# Varella_Std_-_v_1_0.net
KiCad netlist of a schematic drawn in EAGLE
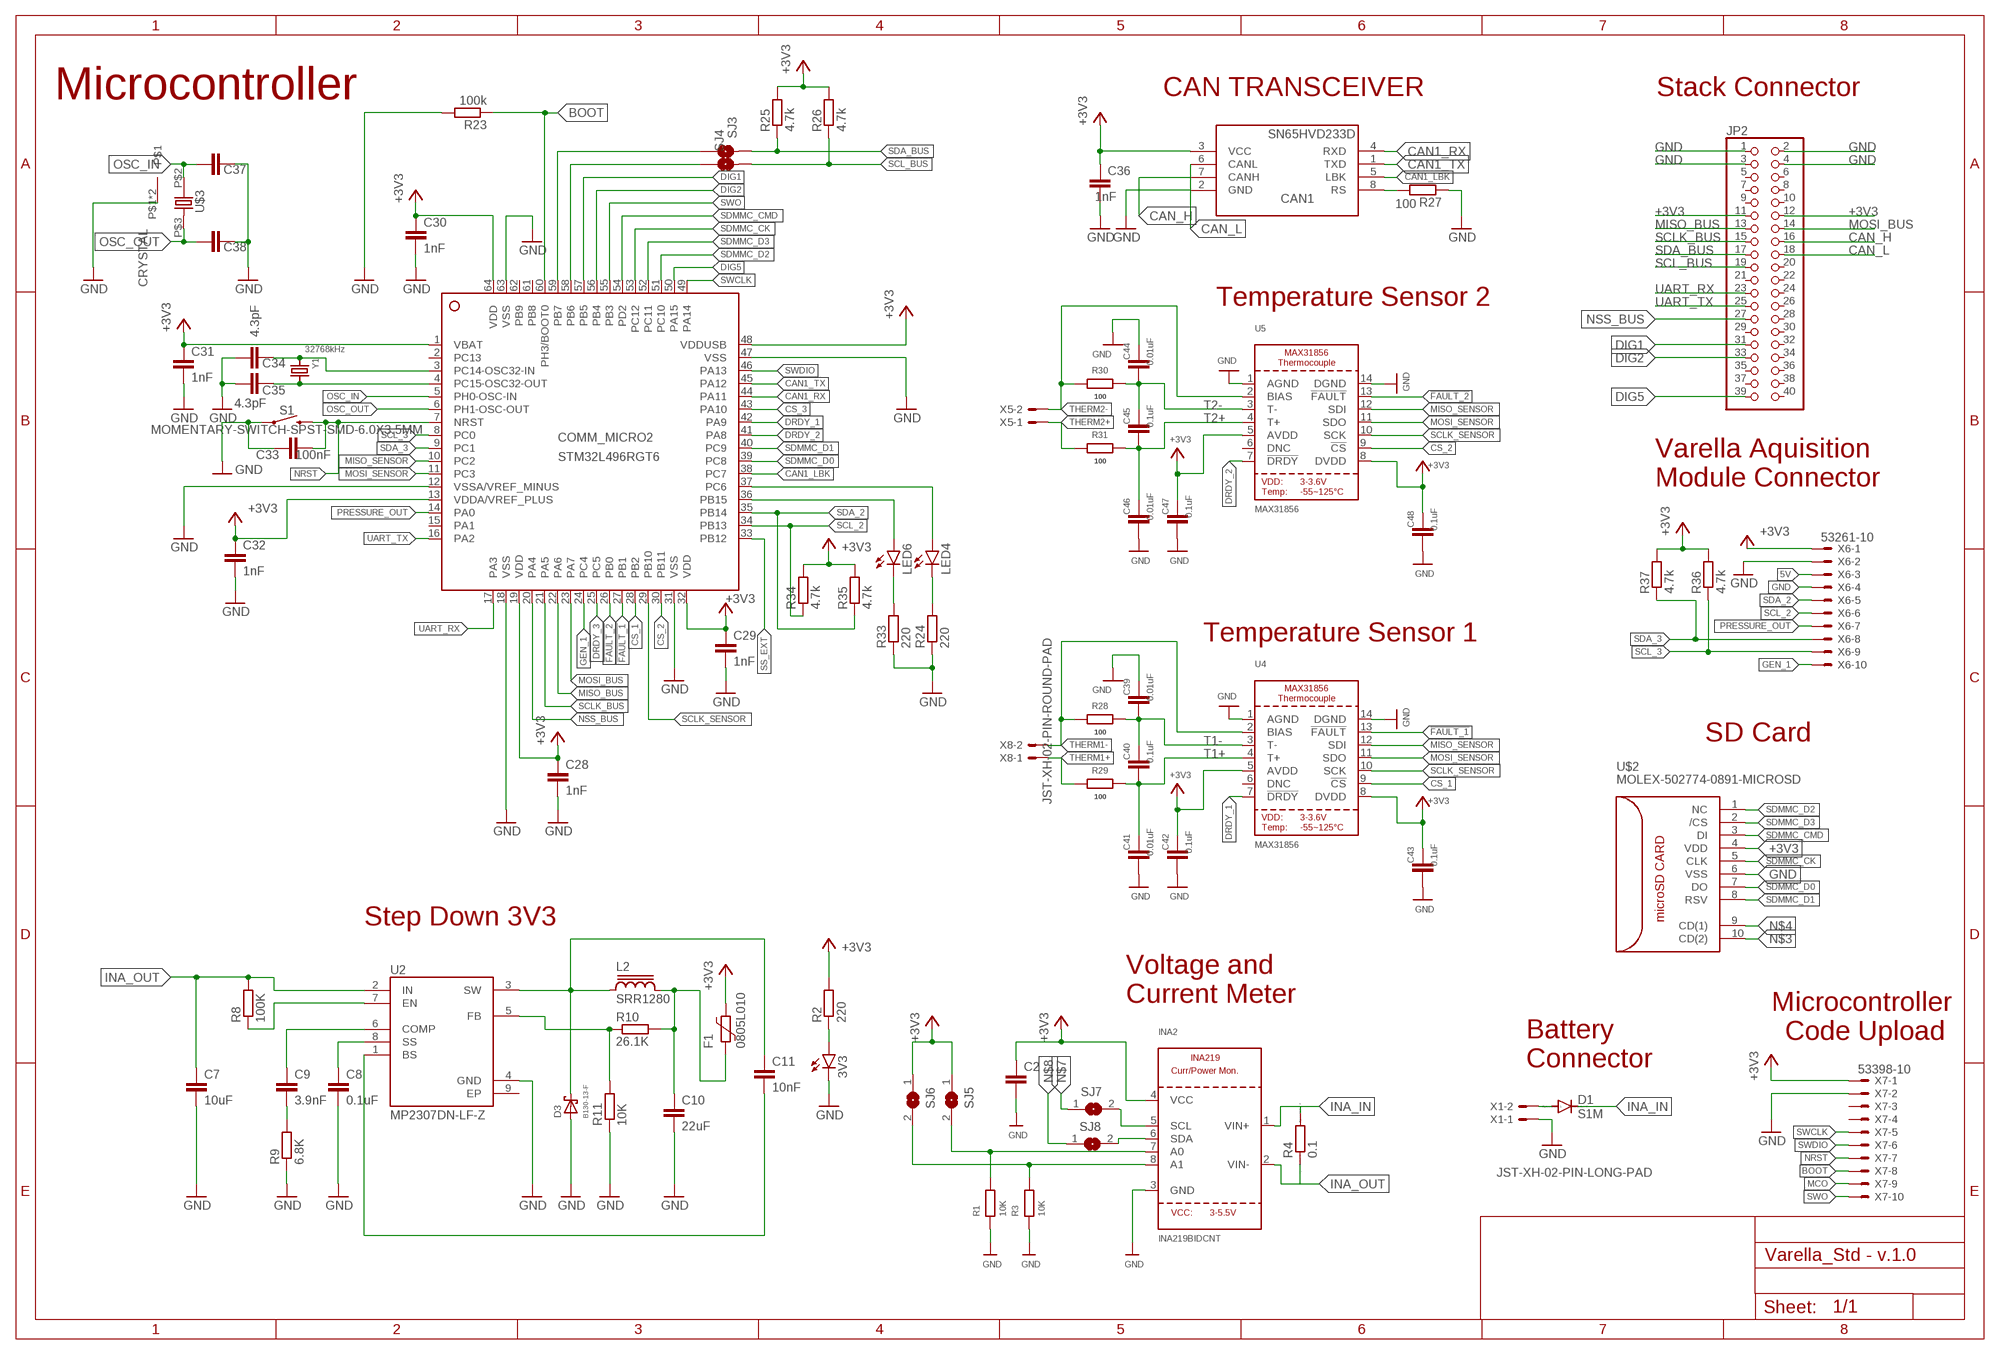
[diagram p0: schematic, sheet 1]

(export (version "E")
  (design (tool "Eeschema 10.0.6"))
  (components
    (comp (ref "3V3")
      (value "LEDCHIP-LED0805")
      (footprint "eagle-import:CHIP-LED0805")
      (libsource (lib "eagle-import") (part "LEDCHIP-LED0805"))
    )
    (comp (ref "C2")
      (value "C-EUC0805")
      (footprint "eagle-import:C0805")
      (libsource (lib "eagle-import") (part "C-EUC0805"))
    )
    (comp (ref "C7")
      (value "10uF")
      (footprint "eagle-import:C0805")
      (libsource (lib "eagle-import") (part "C-EUC0805"))
    )
    (comp (ref "C8")
      (value "0.1uF")
      (footprint "eagle-import:C0805")
      (libsource (lib "eagle-import") (part "C-EUC0805"))
    )
    (comp (ref "C9")
      (value "3.9nF")
      (footprint "eagle-import:C0805")
      (libsource (lib "eagle-import") (part "C-EUC0805"))
    )
    (comp (ref "C10")
      (value "22uF")
      (footprint "eagle-import:C0805")
      (libsource (lib "eagle-import") (part "C-EUC0805"))
    )
    (comp (ref "C11")
      (value "10nF")
      (footprint "eagle-import:C0805")
      (libsource (lib "eagle-import") (part "C-EUC0805"))
    )
    (comp (ref "C28")
      (value "1nF")
      (footprint "eagle-import:C0805")
      (libsource (lib "eagle-import") (part "C-EUC0805"))
    )
    (comp (ref "C29")
      (value "1nF")
      (footprint "eagle-import:C0805")
      (libsource (lib "eagle-import") (part "C-EUC0805"))
    )
    (comp (ref "C30")
      (value "1nF")
      (footprint "eagle-import:C0805")
      (libsource (lib "eagle-import") (part "C-EUC0805"))
    )
    (comp (ref "C31")
      (value "1nF")
      (footprint "eagle-import:C0805")
      (libsource (lib "eagle-import") (part "C-EUC0805"))
    )
    (comp (ref "C32")
      (value "1nF")
      (footprint "eagle-import:C0805")
      (libsource (lib "eagle-import") (part "C-EUC0805"))
    )
    (comp (ref "C33")
      (value "100nF")
      (footprint "eagle-import:C0805")
      (libsource (lib "eagle-import") (part "C-EUC0805"))
    )
    (comp (ref "C34")
      (value "4.3pF")
      (footprint "eagle-import:C0805")
      (libsource (lib "eagle-import") (part "C-EUC0805"))
    )
    (comp (ref "C35")
      (value "4.3pF")
      (footprint "eagle-import:C0805")
      (libsource (lib "eagle-import") (part "C-EUC0805"))
    )
    (comp (ref "C36")
      (value "1nF")
      (footprint "eagle-import:C0805")
      (libsource (lib "eagle-import") (part "C-EUC0805"))
    )
    (comp (ref "C37")
      (value "C-EUC0805")
      (footprint "eagle-import:C0805")
      (libsource (lib "eagle-import") (part "C-EUC0805"))
    )
    (comp (ref "C38")
      (value "C-EUC0805")
      (footprint "eagle-import:C0805")
      (libsource (lib "eagle-import") (part "C-EUC0805"))
    )
    (comp (ref "C39")
      (value "0.01uF")
      (footprint "eagle-import:C0805")
      (libsource (lib "eagle-import") (part "C-EUC0805"))
    )
    (comp (ref "C40")
      (value "0.1uF")
      (footprint "eagle-import:C0805")
      (libsource (lib "eagle-import") (part "C-EUC0805"))
    )
    (comp (ref "C41")
      (value "0.01uF")
      (footprint "eagle-import:C0805")
      (libsource (lib "eagle-import") (part "C-EUC0805"))
    )
    (comp (ref "C42")
      (value "0.1uF")
      (footprint "eagle-import:C0805")
      (libsource (lib "eagle-import") (part "C-EUC0805"))
    )
    (comp (ref "C43")
      (value "0.1uF")
      (footprint "eagle-import:C0805")
      (libsource (lib "eagle-import") (part "C-EUC0805"))
    )
    (comp (ref "C44")
      (value "0.01uF")
      (footprint "eagle-import:C0805")
      (libsource (lib "eagle-import") (part "C-EUC0805"))
    )
    (comp (ref "C45")
      (value "0.1uF")
      (footprint "eagle-import:C0805")
      (libsource (lib "eagle-import") (part "C-EUC0805"))
    )
    (comp (ref "C46")
      (value "0.01uF")
      (footprint "eagle-import:C0805")
      (libsource (lib "eagle-import") (part "C-EUC0805"))
    )
    (comp (ref "C47")
      (value "0.1uF")
      (footprint "eagle-import:C0805")
      (libsource (lib "eagle-import") (part "C-EUC0805"))
    )
    (comp (ref "C48")
      (value "0.1uF")
      (footprint "eagle-import:C0805")
      (libsource (lib "eagle-import") (part "C-EUC0805"))
    )
    (comp (ref "CAN1")
      (value "SN65HVD233D")
      (footprint "eagle-import:SOIC8")
      (fields (field (name "MF") "Texas Instruments"))
      (libsource (lib "eagle-import") (part "SN65HVD233D"))
    )
    (comp (ref "COMM_MICRO2")
      (value "STM32L496RGT6")
      (footprint "eagle-import:LQFP64_10X10")
      (libsource (lib "eagle-import") (part "STM32L496RGT6"))
    )
    (comp (ref "D1")
      (value "S1M")
      (footprint "eagle-import:SMA")
      (libsource (lib "eagle-import") (part "S1M"))
    )
    (comp (ref "D3")
      (value "B130-13-F")
      (footprint "eagle-import:SMA")
      (fields (field (name "MF") "Multicomp"))
      (libsource (lib "eagle-import") (part "B130-13-F"))
    )
    (comp (ref "F1")
      (value "0805L010")
      (footprint "eagle-import:0805L")
      (fields (field (name "MF") "Littelfuse"))
      (libsource (lib "eagle-import") (part "?0805L010"))
    )
    (comp (ref "INA2")
      (value "INA219BIDCNT")
      (footprint "eagle-import:SOT23-8")
      (libsource (lib "eagle-import") (part "INA219"))
    )
    (comp (ref "JP2")
      (value "PINHD-2X20")
      (footprint "eagle-import:2X20")
      (libsource (lib "eagle-import") (part "PINHD-2X20"))
    )
    (comp (ref "L2")
      (value "SRR1280")
      (footprint "eagle-import:SRR1280")
      (libsource (lib "eagle-import") (part "SRR1280"))
    )
    (comp (ref "LED4")
      (value "LEDCHIP-LED0805")
      (footprint "eagle-import:CHIP-LED0805")
      (libsource (lib "eagle-import") (part "LEDCHIP-LED0805"))
    )
    (comp (ref "LED6")
      (value "LEDCHIP-LED0805")
      (footprint "eagle-import:CHIP-LED0805")
      (libsource (lib "eagle-import") (part "LEDCHIP-LED0805"))
    )
    (comp (ref "R1")
      (value "10K")
      (footprint "eagle-import:R0805")
      (libsource (lib "eagle-import") (part "R-EU_R0805"))
    )
    (comp (ref "R2")
      (value "220")
      (footprint "eagle-import:R0805")
      (libsource (lib "eagle-import") (part "R-EU_R0805"))
    )
    (comp (ref "R3")
      (value "10K")
      (footprint "eagle-import:R0805")
      (libsource (lib "eagle-import") (part "R-EU_R0805"))
    )
    (comp (ref "R4")
      (value "0.1")
      (footprint "eagle-import:R2512")
      (libsource (lib "eagle-import") (part "RR2512"))
    )
    (comp (ref "R8")
      (value "100K")
      (footprint "eagle-import:R0805")
      (libsource (lib "eagle-import") (part "R-EU_R0805"))
    )
    (comp (ref "R9")
      (value "6.8K")
      (footprint "eagle-import:R0805")
      (libsource (lib "eagle-import") (part "R-EU_R0805"))
    )
    (comp (ref "R10")
      (value "26.1K")
      (footprint "eagle-import:R0805")
      (libsource (lib "eagle-import") (part "R-EU_R0805"))
    )
    (comp (ref "R11")
      (value "10K")
      (footprint "eagle-import:R0805")
      (libsource (lib "eagle-import") (part "R-EU_R0805"))
    )
    (comp (ref "R23")
      (value "100k")
      (footprint "eagle-import:R0805")
      (libsource (lib "eagle-import") (part "R-EU_R0805"))
    )
    (comp (ref "R24")
      (value "220")
      (footprint "eagle-import:R0805")
      (libsource (lib "eagle-import") (part "R-EU_R0805"))
    )
    (comp (ref "R25")
      (value "4.7k")
      (footprint "eagle-import:R0805")
      (libsource (lib "eagle-import") (part "R-EU_R0805"))
    )
    (comp (ref "R26")
      (value "4.7k")
      (footprint "eagle-import:R0805")
      (libsource (lib "eagle-import") (part "R-EU_R0805"))
    )
    (comp (ref "R27")
      (value "100")
      (footprint "eagle-import:R0805")
      (libsource (lib "eagle-import") (part "R-EU_R0805"))
    )
    (comp (ref "R28")
      (value "100")
      (footprint "eagle-import:R0805")
      (libsource (lib "eagle-import") (part "R-EU_R0805"))
    )
    (comp (ref "R29")
      (value "100")
      (footprint "eagle-import:R0805")
      (libsource (lib "eagle-import") (part "R-EU_R0805"))
    )
    (comp (ref "R30")
      (value "100")
      (footprint "eagle-import:R0805")
      (libsource (lib "eagle-import") (part "R-EU_R0805"))
    )
    (comp (ref "R31")
      (value "100")
      (footprint "eagle-import:R0805")
      (libsource (lib "eagle-import") (part "R-EU_R0805"))
    )
    (comp (ref "R33")
      (value "220")
      (footprint "eagle-import:R0805")
      (libsource (lib "eagle-import") (part "R-EU_R0805"))
    )
    (comp (ref "R34")
      (value "4.7k")
      (footprint "eagle-import:R0805")
      (libsource (lib "eagle-import") (part "R-EU_R0805"))
    )
    (comp (ref "R35")
      (value "4.7k")
      (footprint "eagle-import:R0805")
      (libsource (lib "eagle-import") (part "R-EU_R0805"))
    )
    (comp (ref "R36")
      (value "4.7k")
      (footprint "eagle-import:R0805")
      (libsource (lib "eagle-import") (part "R-EU_R0805"))
    )
    (comp (ref "R37")
      (value "4.7k")
      (footprint "eagle-import:R0805")
      (libsource (lib "eagle-import") (part "R-EU_R0805"))
    )
    (comp (ref "S1")
      (value "MOMENTARY-SWITCH-SPST-SMD-6.0X3.5MM")
      (footprint "eagle-import:TACTILE_SWITCH_SMD_6.0X3.5MM")
      (libsource (lib "eagle-import") (part "MOMENTARY-SWITCH-SPST-SMD-6.0X3.5MM"))
    )
    (comp (ref "SJ3")
      (value "SMD-JUMPER-2")
      (footprint "eagle-import:SMD-JUMPER-2")
      (libsource (lib "eagle-import") (part "SMD-JUMPER-2"))
    )
    (comp (ref "SJ4")
      (value "SMD-JUMPER-2")
      (footprint "eagle-import:SMD-JUMPER-2")
      (libsource (lib "eagle-import") (part "SMD-JUMPER-2"))
    )
    (comp (ref "SJ5")
      (value "SOLDERJUMPERREFLOW_NOPASTE")
      (footprint "eagle-import:SOLDERJUMPER_REFLOW_NOPASTE")
      (libsource (lib "eagle-import") (part "SOLDERJUMPERREFLOW_NOPASTE"))
    )
    (comp (ref "SJ6")
      (value "SOLDERJUMPERREFLOW_NOPASTE")
      (footprint "eagle-import:SOLDERJUMPER_REFLOW_NOPASTE")
      (libsource (lib "eagle-import") (part "SOLDERJUMPERREFLOW_NOPASTE"))
    )
    (comp (ref "SJ7")
      (value "SOLDERJUMPERREFLOW_NOPASTE")
      (footprint "eagle-import:SOLDERJUMPER_REFLOW_NOPASTE")
      (libsource (lib "eagle-import") (part "SOLDERJUMPERREFLOW_NOPASTE"))
    )
    (comp (ref "SJ8")
      (value "SOLDERJUMPERREFLOW_NOPASTE")
      (footprint "eagle-import:SOLDERJUMPER_REFLOW_NOPASTE")
      (libsource (lib "eagle-import") (part "SOLDERJUMPERREFLOW_NOPASTE"))
    )
    (comp (ref "U$2")
      (value "MOLEX-502774-0891-MICROSD")
      (footprint "eagle-import:MOLEX-502774-0891-MICROSD")
      (libsource (lib "eagle-import") (part "MOLEX-502774-0891-MICROSD"))
    )
    (comp (ref "U$3")
      (value "CRYSTAL")
      (footprint "eagle-import:CRYSTAL_SMD")
      (libsource (lib "eagle-import") (part "CRYSTAL"))
    )
    (comp (ref "U2")
      (value "MP2307DN-LF-Z")
      (footprint "eagle-import:SOIC127P600X170-9N")
      (fields (field (name "MF") "Monolithic Power"))
      (libsource (lib "eagle-import") (part "MP2307DN-LF-Z"))
    )
    (comp (ref "U4")
      (value "MAX31856")
      (footprint "eagle-import:TSSOP14")
      (libsource (lib "eagle-import") (part "MAX31856"))
    )
    (comp (ref "U5")
      (value "MAX31856")
      (footprint "eagle-import:TSSOP14")
      (libsource (lib "eagle-import") (part "MAX31856"))
    )
    (comp (ref "X1")
      (value "JST-XH-02-PIN-LONG-PAD")
      (footprint "eagle-import:JST-XH-02-PACKAGE-LONG-PAD")
      (libsource (lib "eagle-import") (part "JST-XH-02-PIN-LONG-PAD"))
    )
    (comp (ref "X5")
      (value "JST-XH-02-PIN-ROUND-PAD")
      (footprint "eagle-import:JST-XH-02-PACKAGE-ROUND-PAD")
      (libsource (lib "eagle-import") (part "JST-XH-02-PIN-ROUND-PAD"))
    )
    (comp (ref "X6")
      (value "53261-10")
      (footprint "eagle-import:53261-10")
      (fields (field (name "MF") "MOLEX"))
      (libsource (lib "eagle-import") (part "con-zenith_17020879_53?-10261"))
    )
    (comp (ref "X7")
      (value "53398-10")
      (footprint "eagle-import:53398-10")
      (fields (field (name "MF") "MOLEX") (field (name "MPN") "53398-1071"))
      (libsource (lib "eagle-import") (part "53?-10398"))
    )
    (comp (ref "X8")
      (value "JST-XH-02-PIN-ROUND-PAD")
      (footprint "eagle-import:JST-XH-02-PACKAGE-ROUND-PAD")
      (libsource (lib "eagle-import") (part "JST-XH-02-PIN-ROUND-PAD"))
    )
    (comp (ref "Y1")
      (value "32768kHz")
      (footprint "eagle-import:CRYSTAL_8X3.8")
      (libsource (lib "eagle-import") (part "CRYSTAL8X3.8SMT"))
    )
  )
  (nets
    (net (code "1") (name "+3V3") (class "Default")
      (node (ref "C2") (pin "1") (pinfunction "1_1") (pintype "passive"))
      (node (ref "C28") (pin "1") (pinfunction "1_1") (pintype "passive"))
      (node (ref "C29") (pin "1") (pinfunction "1_1") (pintype "passive"))
      (node (ref "C30") (pin "1") (pinfunction "1_1") (pintype "passive"))
      (node (ref "C31") (pin "1") (pinfunction "1_1") (pintype "passive"))
      (node (ref "C32") (pin "1") (pinfunction "1_1") (pintype "passive"))
      (node (ref "C36") (pin "1") (pinfunction "1_1") (pintype "passive"))
      (node (ref "C42") (pin "1") (pinfunction "1_1") (pintype "passive"))
      (node (ref "C43") (pin "1") (pinfunction "1_1") (pintype "passive"))
      (node (ref "C47") (pin "1") (pinfunction "1_1") (pintype "passive"))
      (node (ref "C48") (pin "1") (pinfunction "1_1") (pintype "passive"))
      (node (ref "CAN1") (pin "3") (pinfunction "VCC_3") (pintype "power_in"))
      (node (ref "COMM_MICRO2") (pin "1") (pinfunction "VBAT_1") (pintype "passive"))
      (node (ref "COMM_MICRO2") (pin "13") (pinfunction "VDDA/VREF_PLUS_13") (pintype "passive"))
      (node (ref "COMM_MICRO2") (pin "19") (pinfunction "VDD_19") (pintype "power_in"))
      (node (ref "COMM_MICRO2") (pin "32") (pinfunction "VDD_32") (pintype "power_in"))
      (node (ref "COMM_MICRO2") (pin "48") (pinfunction "VDDUSB_48") (pintype "bidirectional"))
      (node (ref "COMM_MICRO2") (pin "64") (pinfunction "VDD_64") (pintype "power_in"))
      (node (ref "F1") (pin "1") (pinfunction "1_1") (pintype "passive"))
      (node (ref "INA2") (pin "4") (pinfunction "VCC_4") (pintype "bidirectional"))
      (node (ref "JP2") (pin "11") (pinfunction "11_11") (pintype "passive"))
      (node (ref "JP2") (pin "12") (pinfunction "12_12") (pintype "passive"))
      (node (ref "R2") (pin "2") (pinfunction "2_2") (pintype "passive"))
      (node (ref "R25") (pin "2") (pinfunction "2_2") (pintype "passive"))
      (node (ref "R26") (pin "2") (pinfunction "2_2") (pintype "passive"))
      (node (ref "R34") (pin "2") (pinfunction "2_2") (pintype "passive"))
      (node (ref "R35") (pin "2") (pinfunction "2_2") (pintype "passive"))
      (node (ref "R36") (pin "2") (pinfunction "2_2") (pintype "passive"))
      (node (ref "R37") (pin "2") (pinfunction "2_2") (pintype "passive"))
      (node (ref "SJ5") (pin "1") (pinfunction "1_1") (pintype "passive"))
      (node (ref "SJ6") (pin "1") (pinfunction "1_1") (pintype "passive"))
      (node (ref "U$2") (pin "4") (pinfunction "VDD_4") (pintype "bidirectional"))
      (node (ref "U4") (pin "5") (pinfunction "AVDD_5") (pintype "power_in"))
      (node (ref "U4") (pin "8") (pinfunction "DVDD_8") (pintype "power_in"))
      (node (ref "U5") (pin "5") (pinfunction "AVDD_5") (pintype "power_in"))
      (node (ref "U5") (pin "8") (pinfunction "DVDD_8") (pintype "power_in"))
      (node (ref "X6") (pin "1") (pinfunction "S_1") (pintype "passive"))
      (node (ref "X7") (pin "1") (pinfunction "S_1") (pintype "passive"))
    )
    (net (code "2") (name "/EP") (class "Default")
      (node (ref "U2") (pin "9") (pinfunction "EP_9") (pintype "power_in"))
    )
    (net (code "3") (name "/T1+") (class "Default")
      (node (ref "C40") (pin "2") (pinfunction "2_2") (pintype "passive"))
      (node (ref "C41") (pin "1") (pinfunction "1_1") (pintype "passive"))
      (node (ref "R29") (pin "2") (pinfunction "2_2") (pintype "passive"))
      (node (ref "U4") (pin "4") (pinfunction "T+_4") (pintype "input"))
    )
    (net (code "4") (name "/T1-") (class "Default")
      (node (ref "C39") (pin "2") (pinfunction "2_2") (pintype "passive"))
      (node (ref "C40") (pin "1") (pinfunction "1_1") (pintype "passive"))
      (node (ref "R28") (pin "2") (pinfunction "2_2") (pintype "passive"))
      (node (ref "U4") (pin "3") (pinfunction "T-_3") (pintype "input"))
    )
    (net (code "5") (name "/T2+") (class "Default")
      (node (ref "C45") (pin "2") (pinfunction "2_2") (pintype "passive"))
      (node (ref "C46") (pin "1") (pinfunction "1_1") (pintype "passive"))
      (node (ref "R31") (pin "2") (pinfunction "2_2") (pintype "passive"))
      (node (ref "U5") (pin "4") (pinfunction "T+_4") (pintype "input"))
    )
    (net (code "6") (name "/T2-") (class "Default")
      (node (ref "C44") (pin "2") (pinfunction "2_2") (pintype "passive"))
      (node (ref "C45") (pin "1") (pinfunction "1_1") (pintype "passive"))
      (node (ref "R30") (pin "2") (pinfunction "2_2") (pintype "passive"))
      (node (ref "U5") (pin "3") (pinfunction "T-_3") (pintype "input"))
    )
    (net (code "7") (name "/~{FAULT_1}") (class "Default")
      (node (ref "COMM_MICRO2") (pin "27") (pinfunction "PB1_27") (pintype "bidirectional"))
      (node (ref "U4") (pin "13") (pinfunction "~{FAULT}_13") (pintype "output"))
    )
    (net (code "8") (name "/~{FAULT_2}") (class "Default")
      (node (ref "COMM_MICRO2") (pin "26") (pinfunction "PB0_26") (pintype "bidirectional"))
      (node (ref "U5") (pin "13") (pinfunction "~{FAULT}_13") (pintype "output"))
    )
    (net (code "9") (name "5V") (class "Default")
      (node (ref "X6") (pin "3") (pinfunction "S_3") (pintype "passive"))
    )
    (net (code "10") (name "BOOT") (class "Default")
      (node (ref "COMM_MICRO2") (pin "60") (pinfunction "PH3/BOOT0_60") (pintype "input"))
      (node (ref "R23") (pin "1") (pinfunction "1_1") (pintype "passive"))
      (node (ref "X7") (pin "8") (pinfunction "S_8") (pintype "passive"))
    )
    (net (code "11") (name "CAN1_LBK") (class "Default")
      (node (ref "CAN1") (pin "5") (pinfunction "LBK_5") (pintype "output"))
      (node (ref "COMM_MICRO2") (pin "38") (pinfunction "PC7_38") (pintype "bidirectional"))
    )
    (net (code "12") (name "CAN1_RX") (class "Default")
      (node (ref "CAN1") (pin "4") (pinfunction "RXD_4") (pintype "output"))
      (node (ref "COMM_MICRO2") (pin "44") (pinfunction "PA11_44") (pintype "bidirectional"))
    )
    (net (code "13") (name "CAN1_TX") (class "Default")
      (node (ref "CAN1") (pin "1") (pinfunction "TXD_1") (pintype "bidirectional"))
      (node (ref "COMM_MICRO2") (pin "45") (pinfunction "PA12_45") (pintype "bidirectional"))
    )
    (net (code "14") (name "CAN_H") (class "Default")
      (node (ref "CAN1") (pin "7") (pinfunction "CANH_7") (pintype "bidirectional"))
      (node (ref "JP2") (pin "16") (pinfunction "16_16") (pintype "passive"))
    )
    (net (code "15") (name "CAN_L") (class "Default")
      (node (ref "CAN1") (pin "6") (pinfunction "CANL_6") (pintype "bidirectional"))
      (node (ref "JP2") (pin "18") (pinfunction "18_18") (pintype "passive"))
    )
    (net (code "16") (name "CS_1") (class "Default")
      (node (ref "COMM_MICRO2") (pin "28") (pinfunction "PB2_28") (pintype "bidirectional"))
      (node (ref "U4") (pin "9") (pinfunction "~{CS}_9") (pintype "input"))
    )
    (net (code "17") (name "CS_2") (class "Default")
      (node (ref "COMM_MICRO2") (pin "30") (pinfunction "PB11_30") (pintype "bidirectional"))
      (node (ref "U5") (pin "9") (pinfunction "~{CS}_9") (pintype "input"))
    )
    (net (code "18") (name "CS_3") (class "Default")
      (node (ref "COMM_MICRO2") (pin "43") (pinfunction "PA10_43") (pintype "bidirectional"))
    )
    (net (code "19") (name "DIG1") (class "Default")
      (node (ref "COMM_MICRO2") (pin "57") (pinfunction "PB5_57") (pintype "bidirectional"))
      (node (ref "JP2") (pin "31") (pinfunction "31_31") (pintype "passive"))
    )
    (net (code "20") (name "DIG2") (class "Default")
      (node (ref "COMM_MICRO2") (pin "56") (pinfunction "PB4_56") (pintype "input"))
      (node (ref "JP2") (pin "33") (pinfunction "33_33") (pintype "passive"))
    )
    (net (code "21") (name "DIG5") (class "Default")
      (node (ref "COMM_MICRO2") (pin "50") (pinfunction "PA15_50") (pintype "input"))
      (node (ref "JP2") (pin "39") (pinfunction "39_39") (pintype "passive"))
    )
    (net (code "22") (name "DRDY_1") (class "Default")
      (node (ref "COMM_MICRO2") (pin "42") (pinfunction "PA9_42") (pintype "bidirectional"))
      (node (ref "U4") (pin "7") (pinfunction "~{DRDY}_7") (pintype "output"))
    )
    (net (code "23") (name "DRDY_2") (class "Default")
      (node (ref "COMM_MICRO2") (pin "41") (pinfunction "PA8_41") (pintype "bidirectional"))
      (node (ref "U5") (pin "7") (pinfunction "~{DRDY}_7") (pintype "output"))
    )
    (net (code "24") (name "DRDY_3") (class "Default")
      (node (ref "COMM_MICRO2") (pin "25") (pinfunction "PC5_25") (pintype "bidirectional"))
    )
    (net (code "25") (name "GEN_1") (class "Default")
      (node (ref "COMM_MICRO2") (pin "24") (pinfunction "PC4_24") (pintype "bidirectional"))
      (node (ref "X6") (pin "10") (pinfunction "S_10") (pintype "passive"))
    )
    (net (code "26") (name "GND") (class "Default")
      (node (ref "3V3") (pin "C") (pinfunction "C_C") (pintype "passive"))
      (node (ref "C10") (pin "2") (pinfunction "2_2") (pintype "passive"))
      (node (ref "C2") (pin "2") (pinfunction "2_2") (pintype "passive"))
      (node (ref "C28") (pin "2") (pinfunction "2_2") (pintype "passive"))
      (node (ref "C29") (pin "2") (pinfunction "2_2") (pintype "passive"))
      (node (ref "C30") (pin "2") (pinfunction "2_2") (pintype "passive"))
      (node (ref "C31") (pin "2") (pinfunction "2_2") (pintype "passive"))
      (node (ref "C32") (pin "2") (pinfunction "2_2") (pintype "passive"))
      (node (ref "C33") (pin "1") (pinfunction "1_1") (pintype "passive"))
      (node (ref "C34") (pin "1") (pinfunction "1_1") (pintype "passive"))
      (node (ref "C35") (pin "1") (pinfunction "1_1") (pintype "passive"))
      (node (ref "C36") (pin "2") (pinfunction "2_2") (pintype "passive"))
      (node (ref "C37") (pin "2") (pinfunction "2_2") (pintype "passive"))
      (node (ref "C38") (pin "2") (pinfunction "2_2") (pintype "passive"))
      (node (ref "C39") (pin "1") (pinfunction "1_1") (pintype "passive"))
      (node (ref "C41") (pin "2") (pinfunction "2_2") (pintype "passive"))
      (node (ref "C42") (pin "2") (pinfunction "2_2") (pintype "passive"))
      (node (ref "C43") (pin "2") (pinfunction "2_2") (pintype "passive"))
      (node (ref "C44") (pin "1") (pinfunction "1_1") (pintype "passive"))
      (node (ref "C46") (pin "2") (pinfunction "2_2") (pintype "passive"))
      (node (ref "C47") (pin "2") (pinfunction "2_2") (pintype "passive"))
      (node (ref "C48") (pin "2") (pinfunction "2_2") (pintype "passive"))
      (node (ref "C7") (pin "2") (pinfunction "2_2") (pintype "passive"))
      (node (ref "C8") (pin "2") (pinfunction "2_2") (pintype "passive"))
      (node (ref "CAN1") (pin "2") (pinfunction "GND_2") (pintype "power_in"))
      (node (ref "COMM_MICRO2") (pin "12") (pinfunction "VSSA/VREF_MINUS_12") (pintype "passive"))
      (node (ref "COMM_MICRO2") (pin "18") (pinfunction "VSS_18") (pintype "power_in"))
      (node (ref "COMM_MICRO2") (pin "31") (pinfunction "VSS_31") (pintype "power_in"))
      (node (ref "COMM_MICRO2") (pin "47") (pinfunction "VSS_47") (pintype "power_in"))
      (node (ref "COMM_MICRO2") (pin "63") (pinfunction "VSS_63") (pintype "power_in"))
      (node (ref "D3") (pin "A") (pinfunction "A_A") (pintype "passive"))
      (node (ref "INA2") (pin "3") (pinfunction "GND_3") (pintype "bidirectional"))
      (node (ref "JP2") (pin "1") (pinfunction "1_1") (pintype "passive"))
      (node (ref "JP2") (pin "2") (pinfunction "2_2") (pintype "passive"))
      (node (ref "JP2") (pin "3") (pinfunction "3_3") (pintype "passive"))
      (node (ref "JP2") (pin "4") (pinfunction "4_4") (pintype "passive"))
      (node (ref "R1") (pin "1") (pinfunction "1_1") (pintype "passive"))
      (node (ref "R11") (pin "1") (pinfunction "1_1") (pintype "passive"))
      (node (ref "R23") (pin "2") (pinfunction "2_2") (pintype "passive"))
      (node (ref "R24") (pin "1") (pinfunction "1_1") (pintype "passive"))
      (node (ref "R27") (pin "1") (pinfunction "1_1") (pintype "passive"))
      (node (ref "R3") (pin "1") (pinfunction "1_1") (pintype "passive"))
      (node (ref "R33") (pin "1") (pinfunction "1_1") (pintype "passive"))
      (node (ref "R9") (pin "1") (pinfunction "1_1") (pintype "passive"))
      (node (ref "S1") (pin "1") (pinfunction "1_1") (pintype "passive"))
      (node (ref "U$2") (pin "6") (pinfunction "VSS_6") (pintype "bidirectional"))
      (node (ref "U$3") (pin "P$1") (pinfunction "P$1_P$1") (pintype "bidirectional"))
      (node (ref "U$3") (pin "P$4") (pinfunction "P$1_P$4") (pintype "bidirectional"))
      (node (ref "U2") (pin "4") (pinfunction "GND_4") (pintype "power_in"))
      (node (ref "U4") (pin "1") (pinfunction "AGND_1") (pintype "power_in"))
      (node (ref "U4") (pin "14") (pinfunction "DGND_14") (pintype "power_in"))
      (node (ref "U5") (pin "1") (pinfunction "AGND_1") (pintype "power_in"))
      (node (ref "U5") (pin "14") (pinfunction "DGND_14") (pintype "power_in"))
      (node (ref "X1") (pin "1") (pinfunction "S_1") (pintype "passive"))
      (node (ref "X6") (pin "2") (pinfunction "S_2") (pintype "passive"))
      (node (ref "X6") (pin "4") (pinfunction "S_4") (pintype "passive"))
      (node (ref "X7") (pin "2") (pinfunction "S_2") (pintype "passive"))
    )
    (net (code "27") (name "INA_IN") (class "Default")
      (node (ref "D1") (pin "C") (pinfunction "C_C") (pintype "passive"))
      (node (ref "INA2") (pin "1") (pinfunction "VIN+_1") (pintype "bidirectional"))
      (node (ref "R4") (pin "2") (pinfunction "2_2") (pintype "passive"))
    )
    (net (code "28") (name "INA_OUT") (class "Default")
      (node (ref "C7") (pin "1") (pinfunction "1_1") (pintype "passive"))
      (node (ref "INA2") (pin "2") (pinfunction "VIN-_2") (pintype "bidirectional"))
      (node (ref "R4") (pin "1") (pinfunction "1_1") (pintype "passive"))
      (node (ref "R8") (pin "2") (pinfunction "2_2") (pintype "passive"))
      (node (ref "U2") (pin "2") (pinfunction "IN_2") (pintype "input"))
    )
    (net (code "29") (name "MCO") (class "Default")
      (node (ref "X7") (pin "9") (pinfunction "S_9") (pintype "passive"))
    )
    (net (code "30") (name "MISO_BUS") (class "Default")
      (node (ref "COMM_MICRO2") (pin "22") (pinfunction "PA6_22") (pintype "bidirectional"))
      (node (ref "JP2") (pin "13") (pinfunction "13_13") (pintype "passive"))
    )
    (net (code "31") (name "MISO_SENSOR") (class "Default")
      (node (ref "COMM_MICRO2") (pin "10") (pinfunction "PC2_10") (pintype "bidirectional"))
      (node (ref "U4") (pin "12") (pinfunction "SDI_12") (pintype "input"))
      (node (ref "U5") (pin "12") (pinfunction "SDI_12") (pintype "input"))
    )
    (net (code "32") (name "MOSI_BUS") (class "Default")
      (node (ref "COMM_MICRO2") (pin "23") (pinfunction "PA7_23") (pintype "bidirectional"))
      (node (ref "JP2") (pin "14") (pinfunction "14_14") (pintype "passive"))
    )
    (net (code "33") (name "MOSI_SENSOR") (class "Default")
      (node (ref "COMM_MICRO2") (pin "11") (pinfunction "PC3_11") (pintype "bidirectional"))
      (node (ref "U4") (pin "11") (pinfunction "SDO_11") (pintype "output"))
      (node (ref "U5") (pin "11") (pinfunction "SDO_11") (pintype "output"))
    )
    (net (code "34") (name "N$3") (class "Default")
      (node (ref "U$2") (pin "10") (pinfunction "CD(2)_10") (pintype "bidirectional"))
    )
    (net (code "35") (name "N$4") (class "Default")
      (node (ref "U$2") (pin "9") (pinfunction "CD(1)_9") (pintype "bidirectional"))
    )
    (net (code "36") (name "N$7") (class "Default")
      (node (ref "INA2") (pin "8") (pinfunction "A1_8") (pintype "bidirectional"))
      (node (ref "R3") (pin "2") (pinfunction "2_2") (pintype "passive"))
      (node (ref "SJ6") (pin "2") (pinfunction "2_2") (pintype "passive"))
      (node (ref "SJ7") (pin "1") (pinfunction "1_1") (pintype "passive"))
    )
    (net (code "37") (name "N$8") (class "Default")
      (node (ref "INA2") (pin "7") (pinfunction "A0_7") (pintype "bidirectional"))
      (node (ref "R1") (pin "2") (pinfunction "2_2") (pintype "passive"))
      (node (ref "SJ5") (pin "2") (pinfunction "2_2") (pintype "passive"))
      (node (ref "SJ8") (pin "1") (pinfunction "1_1") (pintype "passive"))
    )
    (net (code "38") (name "NRST") (class "Default")
      (node (ref "C33") (pin "2") (pinfunction "2_2") (pintype "passive"))
      (node (ref "COMM_MICRO2") (pin "7") (pinfunction "NRST_7") (pintype "input"))
      (node (ref "S1") (pin "2") (pinfunction "2_2") (pintype "passive"))
      (node (ref "X7") (pin "7") (pinfunction "S_7") (pintype "passive"))
    )
    (net (code "39") (name "NSS_BUS") (class "Default")
      (node (ref "COMM_MICRO2") (pin "20") (pinfunction "PA4_20") (pintype "bidirectional"))
      (node (ref "JP2") (pin "27") (pinfunction "27_27") (pintype "passive"))
    )
    (net (code "40") (name "Net-(3V3-PadA)") (class "Default")
      (node (ref "3V3") (pin "A") (pinfunction "A_A") (pintype "passive"))
      (node (ref "R2") (pin "1") (pinfunction "1_1") (pintype "passive"))
    )
    (net (code "41") (name "Net-(C9-Pad2)") (class "Default")
      (node (ref "C9") (pin "2") (pinfunction "2_2") (pintype "passive"))
      (node (ref "R9") (pin "2") (pinfunction "2_2") (pintype "passive"))
    )
    (net (code "42") (name "Net-(C10-Pad1)") (class "Default")
      (node (ref "C10") (pin "1") (pinfunction "1_1") (pintype "passive"))
      (node (ref "F1") (pin "2") (pinfunction "2_2") (pintype "passive"))
      (node (ref "L2") (pin "2") (pinfunction "2_2") (pintype "passive"))
      (node (ref "R10") (pin "2") (pinfunction "2_2") (pintype "passive"))
    )
    (net (code "43") (name "Net-(CAN1-RS)") (class "Default")
      (node (ref "CAN1") (pin "8") (pinfunction "RS_8") (pintype "input"))
      (node (ref "R27") (pin "2") (pinfunction "2_2") (pintype "passive"))
    )
    (net (code "44") (name "Net-(COMM_MICRO2-PB6)") (class "Default")
      (node (ref "COMM_MICRO2") (pin "58") (pinfunction "PB6_58") (pintype "bidirectional"))
      (node (ref "SJ4") (pin "1") (pinfunction "1_1") (pintype "passive"))
    )
    (net (code "45") (name "Net-(COMM_MICRO2-PB7)") (class "Default")
      (node (ref "COMM_MICRO2") (pin "59") (pinfunction "PB7_59") (pintype "bidirectional"))
      (node (ref "SJ3") (pin "1") (pinfunction "1_1") (pintype "passive"))
    )
    (net (code "46") (name "Net-(COMM_MICRO2-PB15)") (class "Default")
      (node (ref "COMM_MICRO2") (pin "36") (pinfunction "PB15_36") (pintype "bidirectional"))
      (node (ref "LED6") (pin "A") (pinfunction "A_A") (pintype "passive"))
    )
    (net (code "47") (name "Net-(COMM_MICRO2-PC6)") (class "Default")
      (node (ref "COMM_MICRO2") (pin "37") (pinfunction "PC6_37") (pintype "bidirectional"))
      (node (ref "LED4") (pin "A") (pinfunction "A_A") (pintype "passive"))
    )
    (net (code "48") (name "Net-(COMM_MICRO2-PC14-OSC32-IN)") (class "Default")
      (node (ref "C34") (pin "2") (pinfunction "2_2") (pintype "passive"))
      (node (ref "COMM_MICRO2") (pin "3") (pinfunction "PC14-OSC32-IN_3") (pintype "bidirectional"))
      (node (ref "Y1") (pin "P$1") (pinfunction "1_P$1") (pintype "passive"))
    )
    (net (code "49") (name "Net-(COMM_MICRO2-PC15-OSC32-OUT)") (class "Default")
      (node (ref "C35") (pin "2") (pinfunction "2_2") (pintype "passive"))
      (node (ref "COMM_MICRO2") (pin "4") (pinfunction "PC15-OSC32-OUT_4") (pintype "bidirectional"))
      (node (ref "Y1") (pin "P$4") (pinfunction "2_P$4") (pintype "passive"))
    )
    (net (code "50") (name "Net-(INA2-SCL)") (class "Default")
      (node (ref "INA2") (pin "5") (pinfunction "SCL_5") (pintype "bidirectional"))
      (node (ref "SJ7") (pin "2") (pinfunction "2_2") (pintype "passive"))
    )
    (net (code "51") (name "Net-(INA2-SDA)") (class "Default")
      (node (ref "INA2") (pin "6") (pinfunction "SDA_6") (pintype "bidirectional"))
      (node (ref "SJ8") (pin "2") (pinfunction "2_2") (pintype "passive"))
    )
    (net (code "52") (name "Net-(LED4-PadC)") (class "Default")
      (node (ref "LED4") (pin "C") (pinfunction "C_C") (pintype "passive"))
      (node (ref "R24") (pin "2") (pinfunction "2_2") (pintype "passive"))
    )
    (net (code "53") (name "Net-(LED6-PadC)") (class "Default")
      (node (ref "LED6") (pin "C") (pinfunction "C_C") (pintype "passive"))
      (node (ref "R33") (pin "2") (pinfunction "2_2") (pintype "passive"))
    )
    (net (code "54") (name "Net-(U2-BS)") (class "Default")
      (node (ref "C11") (pin "2") (pinfunction "2_2") (pintype "passive"))
      (node (ref "U2") (pin "1") (pinfunction "BS_1") (pintype "passive"))
    )
    (net (code "55") (name "Net-(U2-COMP)") (class "Default")
      (node (ref "C9") (pin "1") (pinfunction "1_1") (pintype "passive"))
      (node (ref "U2") (pin "6") (pinfunction "COMP_6") (pintype "passive"))
    )
    (net (code "56") (name "Net-(U2-EN)") (class "Default")
      (node (ref "R8") (pin "1") (pinfunction "1_1") (pintype "passive"))
      (node (ref "U2") (pin "7") (pinfunction "EN_7") (pintype "input"))
    )
    (net (code "57") (name "Net-(U2-FB)") (class "Default")
      (node (ref "R10") (pin "1") (pinfunction "1_1") (pintype "passive"))
      (node (ref "R11") (pin "2") (pinfunction "2_2") (pintype "passive"))
      (node (ref "U2") (pin "5") (pinfunction "FB_5") (pintype "input"))
    )
    (net (code "58") (name "Net-(U2-SS)") (class "Default")
      (node (ref "C8") (pin "1") (pinfunction "1_1") (pintype "passive"))
      (node (ref "U2") (pin "8") (pinfunction "SS_8") (pintype "passive"))
    )
    (net (code "59") (name "Net-(U2-SW)") (class "Default")
      (node (ref "C11") (pin "1") (pinfunction "1_1") (pintype "passive"))
      (node (ref "D3") (pin "C") (pinfunction "C_C") (pintype "passive"))
      (node (ref "L2") (pin "1") (pinfunction "1_1") (pintype "passive"))
      (node (ref "U2") (pin "3") (pinfunction "SW_3") (pintype "output"))
    )
    (net (code "60") (name "Net-(X1B-S)") (class "Default")
      (node (ref "D1") (pin "A") (pinfunction "A_A") (pintype "passive"))
      (node (ref "X1") (pin "2") (pinfunction "S_2") (pintype "passive"))
    )
    (net (code "61") (name "OSC_IN") (class "Default")
      (node (ref "C37") (pin "1") (pinfunction "1_1") (pintype "passive"))
      (node (ref "COMM_MICRO2") (pin "5") (pinfunction "PH0-OSC-IN_5") (pintype "bidirectional"))
      (node (ref "U$3") (pin "P$2") (pinfunction "1_P$2") (pintype "passive"))
    )
    (net (code "62") (name "OSC_OUT") (class "Default")
      (node (ref "C38") (pin "1") (pinfunction "1_1") (pintype "passive"))
      (node (ref "COMM_MICRO2") (pin "6") (pinfunction "PH1-OSC-OUT_6") (pintype "bidirectional"))
      (node (ref "U$3") (pin "P$3") (pinfunction "2_P$3") (pintype "passive"))
    )
    (net (code "63") (name "PRESSURE_OUT") (class "Default")
      (node (ref "COMM_MICRO2") (pin "14") (pinfunction "PA0_14") (pintype "bidirectional"))
      (node (ref "X6") (pin "7") (pinfunction "S_7") (pintype "passive"))
    )
    (net (code "64") (name "SCLK_BUS") (class "Default")
      (node (ref "COMM_MICRO2") (pin "21") (pinfunction "PA5_21") (pintype "bidirectional"))
      (node (ref "JP2") (pin "15") (pinfunction "15_15") (pintype "passive"))
    )
    (net (code "65") (name "SCLK_SENSOR") (class "Default")
      (node (ref "COMM_MICRO2") (pin "29") (pinfunction "PB10_29") (pintype "bidirectional"))
      (node (ref "U4") (pin "10") (pinfunction "SCK_10") (pintype "input"))
      (node (ref "U5") (pin "10") (pinfunction "SCK_10") (pintype "input"))
    )
    (net (code "66") (name "SCL_2") (class "Default")
      (node (ref "COMM_MICRO2") (pin "34") (pinfunction "PB13_34") (pintype "bidirectional"))
      (node (ref "R34") (pin "1") (pinfunction "1_1") (pintype "passive"))
      (node (ref "X6") (pin "6") (pinfunction "S_6") (pintype "passive"))
    )
    (net (code "67") (name "SCL_3") (class "Default")
      (node (ref "COMM_MICRO2") (pin "8") (pinfunction "PC0_8") (pintype "bidirectional"))
      (node (ref "R36") (pin "1") (pinfunction "1_1") (pintype "passive"))
      (node (ref "X6") (pin "9") (pinfunction "S_9") (pintype "passive"))
    )
    (net (code "68") (name "SCL_BUS") (class "Default")
      (node (ref "JP2") (pin "19") (pinfunction "19_19") (pintype "passive"))
      (node (ref "R26") (pin "1") (pinfunction "1_1") (pintype "passive"))
      (node (ref "SJ4") (pin "2") (pinfunction "2_2") (pintype "passive"))
    )
    (net (code "69") (name "SDA_2") (class "Default")
      (node (ref "COMM_MICRO2") (pin "35") (pinfunction "PB14_35") (pintype "bidirectional"))
      (node (ref "R35") (pin "1") (pinfunction "1_1") (pintype "passive"))
      (node (ref "X6") (pin "5") (pinfunction "S_5") (pintype "passive"))
    )
    (net (code "70") (name "SDA_3") (class "Default")
      (node (ref "COMM_MICRO2") (pin "9") (pinfunction "PC1_9") (pintype "bidirectional"))
      (node (ref "R37") (pin "1") (pinfunction "1_1") (pintype "passive"))
      (node (ref "X6") (pin "8") (pinfunction "S_8") (pintype "passive"))
    )
    (net (code "71") (name "SDA_BUS") (class "Default")
      (node (ref "JP2") (pin "17") (pinfunction "17_17") (pintype "passive"))
      (node (ref "R25") (pin "1") (pinfunction "1_1") (pintype "passive"))
      (node (ref "SJ3") (pin "2") (pinfunction "2_2") (pintype "passive"))
    )
    (net (code "72") (name "SDMMC_CK") (class "Default")
      (node (ref "COMM_MICRO2") (pin "53") (pinfunction "PC12_53") (pintype "bidirectional"))
      (node (ref "U$2") (pin "5") (pinfunction "CLK_5") (pintype "bidirectional"))
    )
    (net (code "73") (name "SDMMC_CMD") (class "Default")
      (node (ref "COMM_MICRO2") (pin "54") (pinfunction "PD2_54") (pintype "bidirectional"))
      (node (ref "U$2") (pin "3") (pinfunction "DI_3") (pintype "bidirectional"))
    )
    (net (code "74") (name "SDMMC_D0") (class "Default")
      (node (ref "COMM_MICRO2") (pin "39") (pinfunction "PC8_39") (pintype "bidirectional"))
      (node (ref "U$2") (pin "7") (pinfunction "DO_7") (pintype "bidirectional"))
    )
    (net (code "75") (name "SDMMC_D1") (class "Default")
      (node (ref "COMM_MICRO2") (pin "40") (pinfunction "PC9_40") (pintype "bidirectional"))
      (node (ref "U$2") (pin "8") (pinfunction "RSV_8") (pintype "bidirectional"))
    )
    (net (code "76") (name "SDMMC_D2") (class "Default")
      (node (ref "COMM_MICRO2") (pin "51") (pinfunction "PC10_51") (pintype "bidirectional"))
      (node (ref "U$2") (pin "1") (pinfunction "NC_1") (pintype "bidirectional"))
    )
    (net (code "77") (name "SDMMC_D3") (class "Default")
      (node (ref "COMM_MICRO2") (pin "52") (pinfunction "PC11_52") (pintype "bidirectional"))
      (node (ref "U$2") (pin "2") (pinfunction "/CS_2") (pintype "bidirectional"))
    )
    (net (code "78") (name "SS_EXT") (class "Default")
      (node (ref "COMM_MICRO2") (pin "33") (pinfunction "PB12_33") (pintype "bidirectional"))
    )
    (net (code "79") (name "SWCLK") (class "Default")
      (node (ref "COMM_MICRO2") (pin "49") (pinfunction "PA14_49") (pintype "input"))
      (node (ref "X7") (pin "5") (pinfunction "S_5") (pintype "passive"))
    )
    (net (code "80") (name "SWDIO") (class "Default")
      (node (ref "COMM_MICRO2") (pin "46") (pinfunction "PA13_46") (pintype "input"))
      (node (ref "X7") (pin "6") (pinfunction "S_6") (pintype "passive"))
    )
    (net (code "81") (name "SWO") (class "Default")
      (node (ref "COMM_MICRO2") (pin "55") (pinfunction "PB3_55") (pintype "output"))
      (node (ref "X7") (pin "10") (pinfunction "S_10") (pintype "passive"))
    )
    (net (code "82") (name "THERM1+") (class "Default")
      (node (ref "R29") (pin "1") (pinfunction "1_1") (pintype "passive"))
      (node (ref "X8") (pin "1") (pinfunction "S_1") (pintype "passive"))
    )
    (net (code "83") (name "THERM1-") (class "Default")
      (node (ref "R28") (pin "1") (pinfunction "1_1") (pintype "passive"))
      (node (ref "U4") (pin "2") (pinfunction "BIAS_2") (pintype "power_in"))
      (node (ref "X8") (pin "2") (pinfunction "S_2") (pintype "passive"))
    )
    (net (code "84") (name "THERM2+") (class "Default")
      (node (ref "R31") (pin "1") (pinfunction "1_1") (pintype "passive"))
      (node (ref "X5") (pin "1") (pinfunction "S_1") (pintype "passive"))
    )
    (net (code "85") (name "THERM2-") (class "Default")
      (node (ref "R30") (pin "1") (pinfunction "1_1") (pintype "passive"))
      (node (ref "U5") (pin "2") (pinfunction "BIAS_2") (pintype "power_in"))
      (node (ref "X5") (pin "2") (pinfunction "S_2") (pintype "passive"))
    )
    (net (code "86") (name "UART_RX") (class "Default")
      (node (ref "COMM_MICRO2") (pin "17") (pinfunction "PA3_17") (pintype "bidirectional"))
      (node (ref "JP2") (pin "23") (pinfunction "23_23") (pintype "passive"))
    )
    (net (code "87") (name "UART_TX") (class "Default")
      (node (ref "COMM_MICRO2") (pin "16") (pinfunction "PA2_16") (pintype "bidirectional"))
      (node (ref "JP2") (pin "25") (pinfunction "25_25") (pintype "passive"))
    )
    (net (code "88") (name "unconnected-(COMM_MICRO2-PA1-Pad15)") (class "Default")
      (node (ref "COMM_MICRO2") (pin "15") (pinfunction "PA1_15") (pintype "bidirectional"))
    )
    (net (code "89") (name "unconnected-(COMM_MICRO2-PB8-Pad61)") (class "Default")
      (node (ref "COMM_MICRO2") (pin "61") (pinfunction "PB8_61") (pintype "bidirectional"))
    )
    (net (code "90") (name "unconnected-(COMM_MICRO2-PB9-Pad62)") (class "Default")
      (node (ref "COMM_MICRO2") (pin "62") (pinfunction "PB9_62") (pintype "bidirectional"))
    )
    (net (code "91") (name "unconnected-(COMM_MICRO2-PC13-Pad2)") (class "Default")
      (node (ref "COMM_MICRO2") (pin "2") (pinfunction "PC13_2") (pintype "bidirectional"))
    )
    (net (code "92") (name "unconnected-(JP2-Pad5)") (class "Default")
      (node (ref "JP2") (pin "5") (pinfunction "5_5") (pintype "passive"))
    )
    (net (code "93") (name "unconnected-(JP2-Pad6)") (class "Default")
      (node (ref "JP2") (pin "6") (pinfunction "6_6") (pintype "passive"))
    )
    (net (code "94") (name "unconnected-(JP2-Pad7)") (class "Default")
      (node (ref "JP2") (pin "7") (pinfunction "7_7") (pintype "passive"))
    )
    (net (code "95") (name "unconnected-(JP2-Pad8)") (class "Default")
      (node (ref "JP2") (pin "8") (pinfunction "8_8") (pintype "passive"))
    )
    (net (code "96") (name "unconnected-(JP2-Pad9)") (class "Default")
      (node (ref "JP2") (pin "9") (pinfunction "9_9") (pintype "passive"))
    )
    (net (code "97") (name "unconnected-(JP2-Pad10)") (class "Default")
      (node (ref "JP2") (pin "10") (pinfunction "10_10") (pintype "passive"))
    )
    (net (code "98") (name "unconnected-(JP2-Pad20)") (class "Default")
      (node (ref "JP2") (pin "20") (pinfunction "20_20") (pintype "passive"))
    )
    (net (code "99") (name "unconnected-(JP2-Pad21)") (class "Default")
      (node (ref "JP2") (pin "21") (pinfunction "21_21") (pintype "passive"))
    )
    (net (code "100") (name "unconnected-(JP2-Pad22)") (class "Default")
      (node (ref "JP2") (pin "22") (pinfunction "22_22") (pintype "passive"))
    )
    (net (code "101") (name "unconnected-(JP2-Pad24)") (class "Default")
      (node (ref "JP2") (pin "24") (pinfunction "24_24") (pintype "passive"))
    )
    (net (code "102") (name "unconnected-(JP2-Pad26)") (class "Default")
      (node (ref "JP2") (pin "26") (pinfunction "26_26") (pintype "passive"))
    )
    (net (code "103") (name "unconnected-(JP2-Pad28)") (class "Default")
      (node (ref "JP2") (pin "28") (pinfunction "28_28") (pintype "passive"))
    )
    (net (code "104") (name "unconnected-(JP2-Pad29)") (class "Default")
      (node (ref "JP2") (pin "29") (pinfunction "29_29") (pintype "passive"))
    )
    (net (code "105") (name "unconnected-(JP2-Pad30)") (class "Default")
      (node (ref "JP2") (pin "30") (pinfunction "30_30") (pintype "passive"))
    )
    (net (code "106") (name "unconnected-(JP2-Pad32)") (class "Default")
      (node (ref "JP2") (pin "32") (pinfunction "32_32") (pintype "passive"))
    )
    (net (code "107") (name "unconnected-(JP2-Pad34)") (class "Default")
      (node (ref "JP2") (pin "34") (pinfunction "34_34") (pintype "passive"))
    )
    (net (code "108") (name "unconnected-(JP2-Pad35)") (class "Default")
      (node (ref "JP2") (pin "35") (pinfunction "35_35") (pintype "passive"))
    )
    (net (code "109") (name "unconnected-(JP2-Pad36)") (class "Default")
      (node (ref "JP2") (pin "36") (pinfunction "36_36") (pintype "passive"))
    )
    (net (code "110") (name "unconnected-(JP2-Pad37)") (class "Default")
      (node (ref "JP2") (pin "37") (pinfunction "37_37") (pintype "passive"))
    )
    (net (code "111") (name "unconnected-(JP2-Pad38)") (class "Default")
      (node (ref "JP2") (pin "38") (pinfunction "38_38") (pintype "passive"))
    )
    (net (code "112") (name "unconnected-(JP2-Pad40)") (class "Default")
      (node (ref "JP2") (pin "40") (pinfunction "40_40") (pintype "passive"))
    )
    (net (code "113") (name "unconnected-(U4-DNC-Pad6)") (class "Default")
      (node (ref "U4") (pin "6") (pinfunction "DNC_6") (pintype "no_connect"))
    )
    (net (code "114") (name "unconnected-(U5-DNC-Pad6)") (class "Default")
      (node (ref "U5") (pin "6") (pinfunction "DNC_6") (pintype "no_connect"))
    )
    (net (code "115") (name "unconnected-(X7D-S-Pad3)") (class "Default")
      (node (ref "X7") (pin "3") (pinfunction "S_3") (pintype "passive"))
    )
    (net (code "116") (name "unconnected-(X7E-S-Pad4)") (class "Default")
      (node (ref "X7") (pin "4") (pinfunction "S_4") (pintype "passive"))
    )
  )
)
